# picoKey_2401.net
KiCad netlist of a schematic drawn in EAGLE
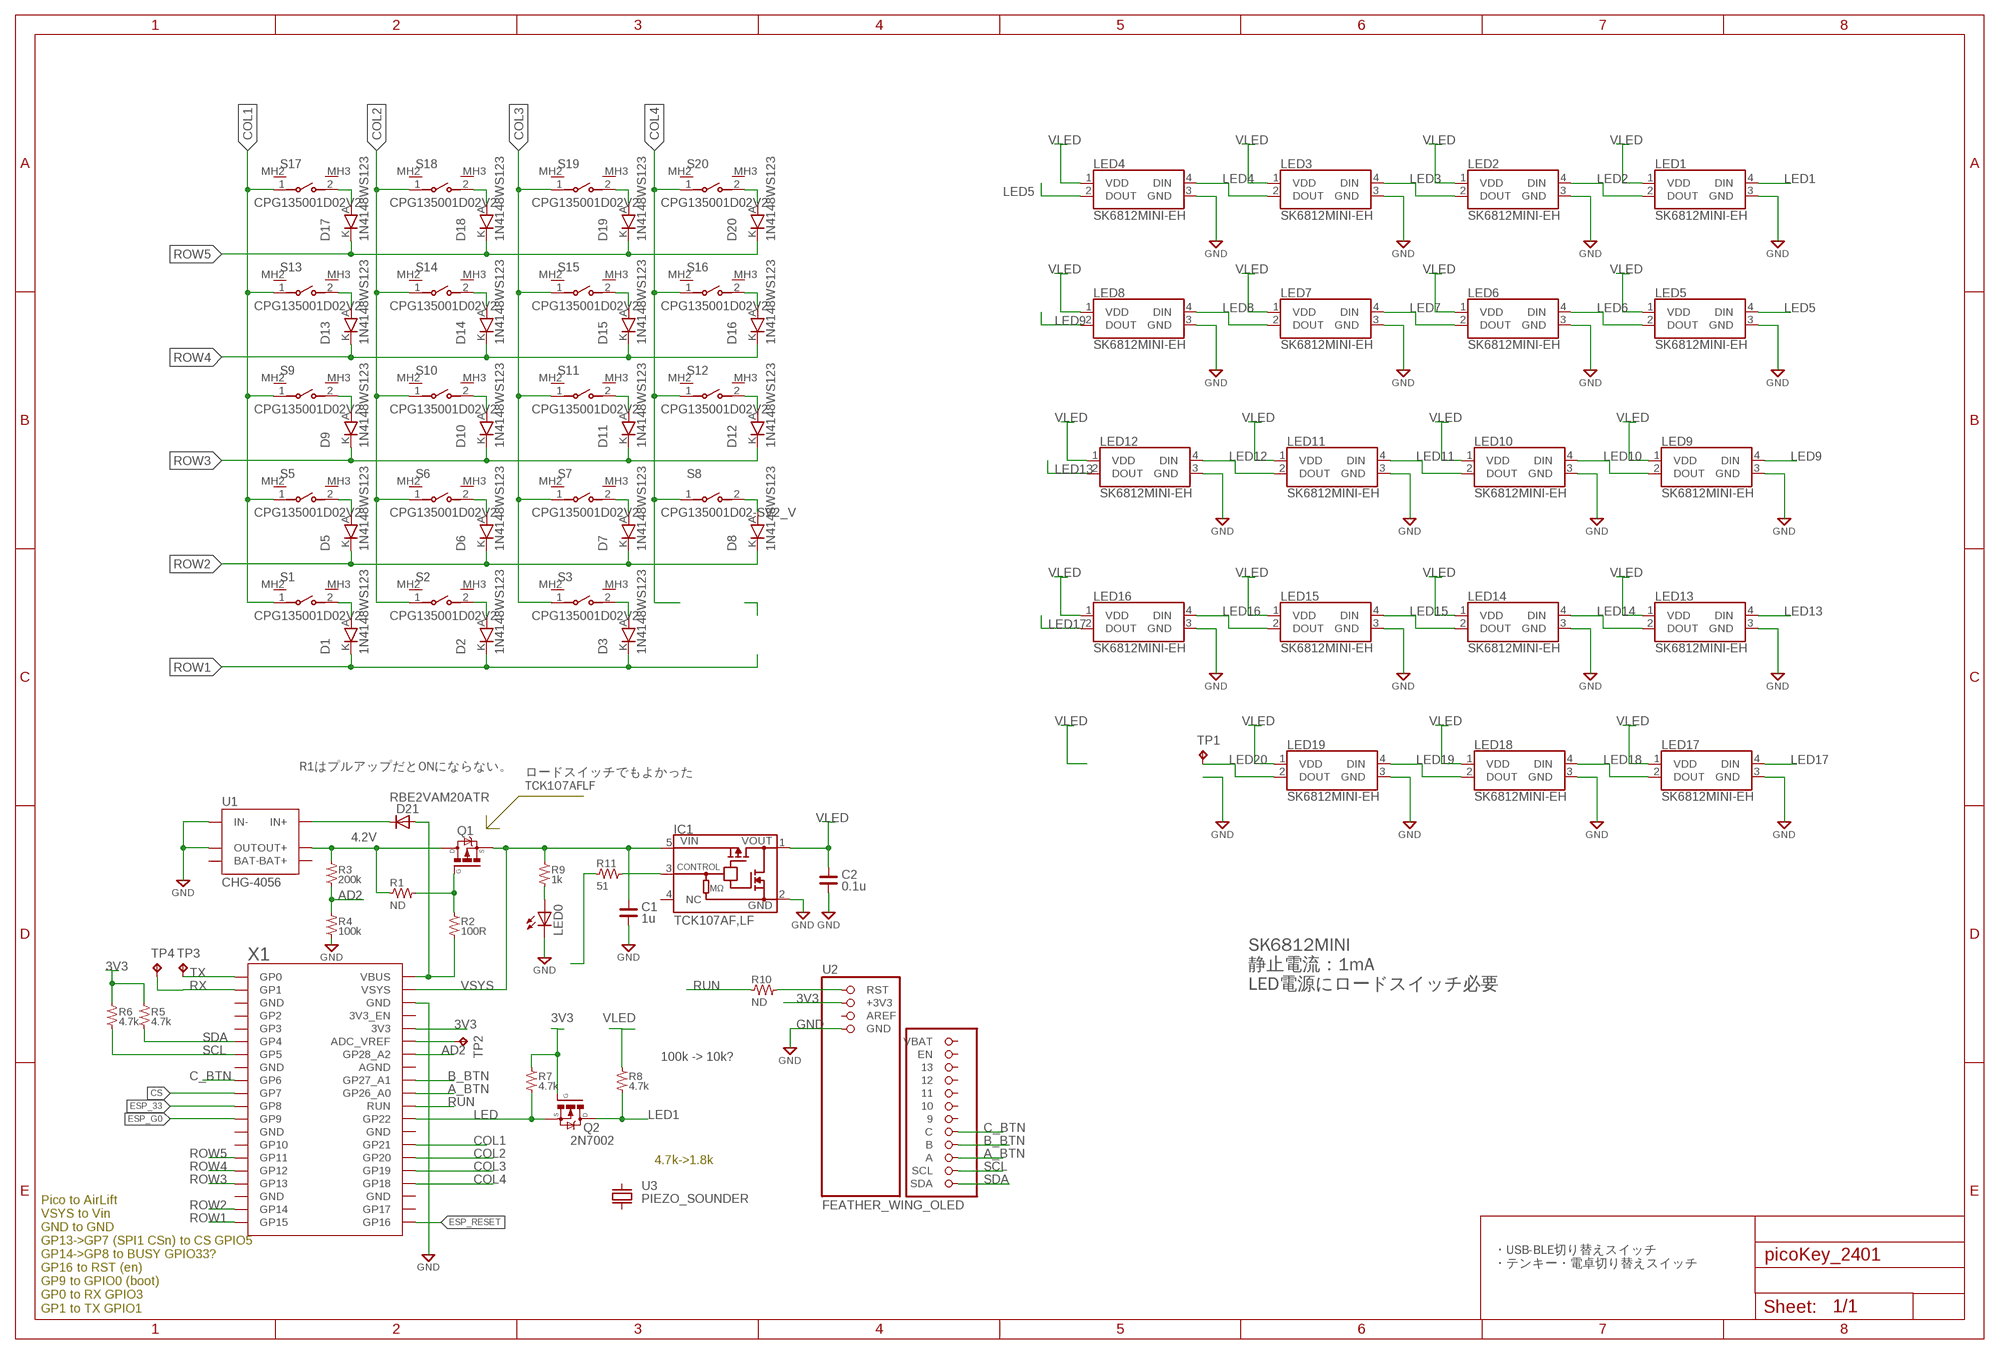
[diagram p0: schematic, sheet 1]

(export (version "E")
  (design (tool "Eeschema 10.0.6"))
  (components
    (comp (ref "C1")
      (value "1u")
      (footprint "eagle-import:C0603")
      (libsource (lib "eagle-import") (part "C_0603"))
    )
    (comp (ref "C2")
      (value "0.1u")
      (footprint "eagle-import:C0603")
      (libsource (lib "eagle-import") (part "C_0603"))
    )
    (comp (ref "D1")
      (value "1N4148WS123")
      (footprint "eagle-import:SOD-123")
      (libsource (lib "eagle-import") (part "1N4148WS123"))
    )
    (comp (ref "D2")
      (value "1N4148WS123")
      (footprint "eagle-import:SOD-123")
      (libsource (lib "eagle-import") (part "1N4148WS123"))
    )
    (comp (ref "D3")
      (value "1N4148WS123")
      (footprint "eagle-import:SOD-123")
      (libsource (lib "eagle-import") (part "1N4148WS123"))
    )
    (comp (ref "D5")
      (value "1N4148WS123")
      (footprint "eagle-import:SOD-123")
      (libsource (lib "eagle-import") (part "1N4148WS123"))
    )
    (comp (ref "D6")
      (value "1N4148WS123")
      (footprint "eagle-import:SOD-123")
      (libsource (lib "eagle-import") (part "1N4148WS123"))
    )
    (comp (ref "D7")
      (value "1N4148WS123")
      (footprint "eagle-import:SOD-123")
      (libsource (lib "eagle-import") (part "1N4148WS123"))
    )
    (comp (ref "D8")
      (value "1N4148WS123")
      (footprint "eagle-import:SOD-123")
      (libsource (lib "eagle-import") (part "1N4148WS123"))
    )
    (comp (ref "D9")
      (value "1N4148WS123")
      (footprint "eagle-import:SOD-123")
      (libsource (lib "eagle-import") (part "1N4148WS123"))
    )
    (comp (ref "D10")
      (value "1N4148WS123")
      (footprint "eagle-import:SOD-123")
      (libsource (lib "eagle-import") (part "1N4148WS123"))
    )
    (comp (ref "D11")
      (value "1N4148WS123")
      (footprint "eagle-import:SOD-123")
      (libsource (lib "eagle-import") (part "1N4148WS123"))
    )
    (comp (ref "D12")
      (value "1N4148WS123")
      (footprint "eagle-import:SOD-123")
      (libsource (lib "eagle-import") (part "1N4148WS123"))
    )
    (comp (ref "D13")
      (value "1N4148WS123")
      (footprint "eagle-import:SOD-123")
      (libsource (lib "eagle-import") (part "1N4148WS123"))
    )
    (comp (ref "D14")
      (value "1N4148WS123")
      (footprint "eagle-import:SOD-123")
      (libsource (lib "eagle-import") (part "1N4148WS123"))
    )
    (comp (ref "D15")
      (value "1N4148WS123")
      (footprint "eagle-import:SOD-123")
      (libsource (lib "eagle-import") (part "1N4148WS123"))
    )
    (comp (ref "D16")
      (value "1N4148WS123")
      (footprint "eagle-import:SOD-123")
      (libsource (lib "eagle-import") (part "1N4148WS123"))
    )
    (comp (ref "D17")
      (value "1N4148WS123")
      (footprint "eagle-import:SOD-123")
      (libsource (lib "eagle-import") (part "1N4148WS123"))
    )
    (comp (ref "D18")
      (value "1N4148WS123")
      (footprint "eagle-import:SOD-123")
      (libsource (lib "eagle-import") (part "1N4148WS123"))
    )
    (comp (ref "D19")
      (value "1N4148WS123")
      (footprint "eagle-import:SOD-123")
      (libsource (lib "eagle-import") (part "1N4148WS123"))
    )
    (comp (ref "D20")
      (value "1N4148WS123")
      (footprint "eagle-import:SOD-123")
      (libsource (lib "eagle-import") (part "1N4148WS123"))
    )
    (comp (ref "D21")
      (value "RBE2VAM20ATR")
      (footprint "eagle-import:SOD-123")
      (libsource (lib "eagle-import") (part "DIODE123"))
    )
    (comp (ref "IC1")
      (value "TCK107AF,LF")
      (footprint "eagle-import:SMV_1")
      (fields
        (field (name "ARROW_PART_NUMBER") "TCK106AF,LF")
        (field (name "MOUSER_PART_NUMBER") "757-TCK106AFLF")
      )
      (libsource (lib "eagle-import") (part "TCK107AF,LF"))
    )
    (comp (ref "LED0")
      (value "LEDCHIP-LED0603")
      (footprint "eagle-import:CHIP-LED0603")
      (libsource (lib "eagle-import") (part "LEDCHIP-LED0603"))
    )
    (comp (ref "LED1")
      (value "SK6812MINI-EH")
      (footprint "eagle-import:SK6812MINIE-H")
      (libsource (lib "eagle-import") (part "SK6812MINI-EH"))
    )
    (comp (ref "LED2")
      (value "SK6812MINI-EH")
      (footprint "eagle-import:SK6812MINIE-H")
      (libsource (lib "eagle-import") (part "SK6812MINI-EH"))
    )
    (comp (ref "LED3")
      (value "SK6812MINI-EH")
      (footprint "eagle-import:SK6812MINIE-H")
      (libsource (lib "eagle-import") (part "SK6812MINI-EH"))
    )
    (comp (ref "LED4")
      (value "SK6812MINI-EH")
      (footprint "eagle-import:SK6812MINIE-H")
      (libsource (lib "eagle-import") (part "SK6812MINI-EH"))
    )
    (comp (ref "LED5")
      (value "SK6812MINI-EH")
      (footprint "eagle-import:SK6812MINIE-H")
      (libsource (lib "eagle-import") (part "SK6812MINI-EH"))
    )
    (comp (ref "LED6")
      (value "SK6812MINI-EH")
      (footprint "eagle-import:SK6812MINIE-H")
      (libsource (lib "eagle-import") (part "SK6812MINI-EH"))
    )
    (comp (ref "LED7")
      (value "SK6812MINI-EH")
      (footprint "eagle-import:SK6812MINIE-H")
      (libsource (lib "eagle-import") (part "SK6812MINI-EH"))
    )
    (comp (ref "LED8")
      (value "SK6812MINI-EH")
      (footprint "eagle-import:SK6812MINIE-H")
      (libsource (lib "eagle-import") (part "SK6812MINI-EH"))
    )
    (comp (ref "LED9")
      (value "SK6812MINI-EH")
      (footprint "eagle-import:SK6812MINIE-H")
      (libsource (lib "eagle-import") (part "SK6812MINI-EH"))
    )
    (comp (ref "LED10")
      (value "SK6812MINI-EH")
      (footprint "eagle-import:SK6812MINIE-H")
      (libsource (lib "eagle-import") (part "SK6812MINI-EH"))
    )
    (comp (ref "LED11")
      (value "SK6812MINI-EH")
      (footprint "eagle-import:SK6812MINIE-H")
      (libsource (lib "eagle-import") (part "SK6812MINI-EH"))
    )
    (comp (ref "LED12")
      (value "SK6812MINI-EH")
      (footprint "eagle-import:SK6812MINIE-H")
      (libsource (lib "eagle-import") (part "SK6812MINI-EH"))
    )
    (comp (ref "LED13")
      (value "SK6812MINI-EH")
      (footprint "eagle-import:SK6812MINIE-H")
      (libsource (lib "eagle-import") (part "SK6812MINI-EH"))
    )
    (comp (ref "LED14")
      (value "SK6812MINI-EH")
      (footprint "eagle-import:SK6812MINIE-H")
      (libsource (lib "eagle-import") (part "SK6812MINI-EH"))
    )
    (comp (ref "LED15")
      (value "SK6812MINI-EH")
      (footprint "eagle-import:SK6812MINIE-H")
      (libsource (lib "eagle-import") (part "SK6812MINI-EH"))
    )
    (comp (ref "LED16")
      (value "SK6812MINI-EH")
      (footprint "eagle-import:SK6812MINIE-H")
      (libsource (lib "eagle-import") (part "SK6812MINI-EH"))
    )
    (comp (ref "LED17")
      (value "SK6812MINI-EH")
      (footprint "eagle-import:SK6812MINIE-H")
      (libsource (lib "eagle-import") (part "SK6812MINI-EH"))
    )
    (comp (ref "LED18")
      (value "SK6812MINI-EH")
      (footprint "eagle-import:SK6812MINIE-H")
      (libsource (lib "eagle-import") (part "SK6812MINI-EH"))
    )
    (comp (ref "LED19")
      (value "SK6812MINI-EH")
      (footprint "eagle-import:SK6812MINIE-H")
      (libsource (lib "eagle-import") (part "SK6812MINI-EH"))
    )
    (comp (ref "Q1")
      (value "MOSFET-P")
      (footprint "eagle-import:SOT-23")
      (libsource (lib "eagle-import") (part "MOSFET-P"))
    )
    (comp (ref "Q2")
      (value "2N7002")
      (footprint "eagle-import:SOT-23")
      (libsource (lib "eagle-import") (part "MOSFET-NSOT-23"))
    )
    (comp (ref "R1")
      (value "ND")
      (footprint "eagle-import:R0603")
      (libsource (lib "eagle-import") (part "R_0603"))
    )
    (comp (ref "R2")
      (value "100R")
      (footprint "eagle-import:R0603")
      (libsource (lib "eagle-import") (part "R_0603"))
    )
    (comp (ref "R3")
      (value "200k")
      (footprint "eagle-import:R0603")
      (libsource (lib "eagle-import") (part "R_0603"))
    )
    (comp (ref "R4")
      (value "100k")
      (footprint "eagle-import:R0603")
      (libsource (lib "eagle-import") (part "R_0603"))
    )
    (comp (ref "R5")
      (value "4.7k")
      (footprint "eagle-import:R0603")
      (libsource (lib "eagle-import") (part "R_0603"))
    )
    (comp (ref "R6")
      (value "4.7k")
      (footprint "eagle-import:R0603")
      (libsource (lib "eagle-import") (part "R_0603"))
    )
    (comp (ref "R7")
      (value "4.7k")
      (footprint "eagle-import:R0603")
      (libsource (lib "eagle-import") (part "R_0603"))
    )
    (comp (ref "R8")
      (value "4.7k")
      (footprint "eagle-import:R0603")
      (libsource (lib "eagle-import") (part "R_0603"))
    )
    (comp (ref "R9")
      (value "1k")
      (footprint "eagle-import:R0603")
      (libsource (lib "eagle-import") (part "R_0603"))
    )
    (comp (ref "R10")
      (value "ND")
      (footprint "eagle-import:R0603")
      (libsource (lib "eagle-import") (part "R_0603"))
    )
    (comp (ref "R11")
      (value "51")
      (footprint "eagle-import:R0603")
      (libsource (lib "eagle-import") (part "R_0603"))
    )
    (comp (ref "S1")
      (value "CPG135001D02V2")
      (footprint "eagle-import:KAILH_CHOC_V2")
      (libsource (lib "eagle-import") (part "CPG135001D02V2"))
    )
    (comp (ref "S2")
      (value "CPG135001D02V2")
      (footprint "eagle-import:KAILH_CHOC_V2")
      (libsource (lib "eagle-import") (part "CPG135001D02V2"))
    )
    (comp (ref "S3")
      (value "CPG135001D02V2")
      (footprint "eagle-import:KAILH_CHOC_V2")
      (libsource (lib "eagle-import") (part "CPG135001D02V2"))
    )
    (comp (ref "S5")
      (value "CPG135001D02V2")
      (footprint "eagle-import:KAILH_CHOC_V2")
      (libsource (lib "eagle-import") (part "CPG135001D02V2"))
    )
    (comp (ref "S6")
      (value "CPG135001D02V2")
      (footprint "eagle-import:KAILH_CHOC_V2")
      (libsource (lib "eagle-import") (part "CPG135001D02V2"))
    )
    (comp (ref "S7")
      (value "CPG135001D02V2")
      (footprint "eagle-import:KAILH_CHOC_V2")
      (libsource (lib "eagle-import") (part "CPG135001D02V2"))
    )
    (comp (ref "S8")
      (value "CPG135001D02-SV2_V")
      (footprint "eagle-import:KAILH_CHOC_V2_V")
      (libsource (lib "eagle-import") (part "CPG135001D02-SV2_V"))
    )
    (comp (ref "S9")
      (value "CPG135001D02V2")
      (footprint "eagle-import:KAILH_CHOC_V2")
      (libsource (lib "eagle-import") (part "CPG135001D02V2"))
    )
    (comp (ref "S10")
      (value "CPG135001D02V2")
      (footprint "eagle-import:KAILH_CHOC_V2")
      (libsource (lib "eagle-import") (part "CPG135001D02V2"))
    )
    (comp (ref "S11")
      (value "CPG135001D02V2")
      (footprint "eagle-import:KAILH_CHOC_V2")
      (libsource (lib "eagle-import") (part "CPG135001D02V2"))
    )
    (comp (ref "S12")
      (value "CPG135001D02V2")
      (footprint "eagle-import:KAILH_CHOC_V2")
      (libsource (lib "eagle-import") (part "CPG135001D02V2"))
    )
    (comp (ref "S13")
      (value "CPG135001D02V2")
      (footprint "eagle-import:KAILH_CHOC_V2")
      (libsource (lib "eagle-import") (part "CPG135001D02V2"))
    )
    (comp (ref "S14")
      (value "CPG135001D02V2")
      (footprint "eagle-import:KAILH_CHOC_V2")
      (libsource (lib "eagle-import") (part "CPG135001D02V2"))
    )
    (comp (ref "S15")
      (value "CPG135001D02V2")
      (footprint "eagle-import:KAILH_CHOC_V2")
      (libsource (lib "eagle-import") (part "CPG135001D02V2"))
    )
    (comp (ref "S16")
      (value "CPG135001D02V2")
      (footprint "eagle-import:KAILH_CHOC_V2")
      (libsource (lib "eagle-import") (part "CPG135001D02V2"))
    )
    (comp (ref "S17")
      (value "CPG135001D02V2")
      (footprint "eagle-import:KAILH_CHOC_V2")
      (libsource (lib "eagle-import") (part "CPG135001D02V2"))
    )
    (comp (ref "S18")
      (value "CPG135001D02V2")
      (footprint "eagle-import:KAILH_CHOC_V2")
      (libsource (lib "eagle-import") (part "CPG135001D02V2"))
    )
    (comp (ref "S19")
      (value "CPG135001D02V2")
      (footprint "eagle-import:KAILH_CHOC_V2")
      (libsource (lib "eagle-import") (part "CPG135001D02V2"))
    )
    (comp (ref "S20")
      (value "CPG135001D02V2")
      (footprint "eagle-import:KAILH_CHOC_V2")
      (libsource (lib "eagle-import") (part "CPG135001D02V2"))
    )
    (comp (ref "TP1")
      (value "TPTP06R")
      (footprint "eagle-import:TP06R")
      (libsource (lib "eagle-import") (part "TPTP06R"))
    )
    (comp (ref "TP2")
      (value "TPTP06R")
      (footprint "eagle-import:TP06R")
      (libsource (lib "eagle-import") (part "TPTP06R"))
    )
    (comp (ref "TP3")
      (value "TPTP06R")
      (footprint "eagle-import:TP06R")
      (libsource (lib "eagle-import") (part "TPTP06R"))
    )
    (comp (ref "TP4")
      (value "TPTP06R")
      (footprint "eagle-import:TP06R")
      (libsource (lib "eagle-import") (part "TPTP06R"))
    )
    (comp (ref "U1")
      (value "CHG-4056")
      (footprint "eagle-import:CHG-4056")
      (libsource (lib "eagle-import") (part "CHG-4056"))
    )
    (comp (ref "U2")
      (value "FEATHER_WING_OLED")
      (footprint "eagle-import:FEATHER_WING_OLED")
      (libsource (lib "eagle-import") (part "FEATHER_WING_OLED"))
    )
    (comp (ref "U3")
      (value "PIEZO_SOUNDER")
      (footprint "eagle-import:DINAMIC-SPK")
      (libsource (lib "eagle-import") (part "PIEZO_SOUNDER"))
    )
    (comp (ref "X1")
      (value "RASPBERRYPI_PICO_RPI_PICO_MY-MY")
      (footprint "eagle-import:RASPBERRYPI_PICO_RPI_PICO_MY")
      (libsource (lib "eagle-import") (part "RASPBERRYPI_PICO_RPI_PICO_MY-MY"))
    )
  )
  (nets
    (net (code "1") (name "/3V3") (class "Default")
      (node (ref "Q2") (pin "3") (pinfunction "G_3") (pintype "passive"))
      (node (ref "R5") (pin "2") (pinfunction "2_2") (pintype "passive"))
      (node (ref "R6") (pin "2") (pinfunction "2_2") (pintype "passive"))
      (node (ref "R7") (pin "1") (pinfunction "1_1") (pintype "passive"))
      (node (ref "U2") (pin "15") (pinfunction "+3V3_15") (pintype "passive"))
      (node (ref "X1") (pin "3V3") (pinfunction "3V3_3V3") (pintype "bidirectional"))
    )
    (net (code "2") (name "/4.2V") (class "Default")
      (node (ref "Q1") (pin "2") (pinfunction "D_2") (pintype "passive"))
      (node (ref "R1") (pin "1") (pinfunction "1_1") (pintype "passive"))
      (node (ref "R3") (pin "2") (pinfunction "2_2") (pintype "passive"))
      (node (ref "U1") (pin "OUT+") (pinfunction "OUT+_OUT+") (pintype "bidirectional"))
    )
    (net (code "3") (name "/AD2") (class "Default")
      (node (ref "R3") (pin "1") (pinfunction "1_1") (pintype "passive"))
      (node (ref "R4") (pin "2") (pinfunction "2_2") (pintype "passive"))
      (node (ref "X1") (pin "GP28_A2") (pinfunction "GP28_A2_GP28_A2") (pintype "bidirectional"))
    )
    (net (code "4") (name "/A_BTN") (class "Default")
      (node (ref "U2") (pin "26") (pinfunction "A_26") (pintype "passive"))
      (node (ref "X1") (pin "GP26_A0") (pinfunction "GP26_A0_GP26_A0") (pintype "bidirectional"))
    )
    (net (code "5") (name "/B_BTN") (class "Default")
      (node (ref "U2") (pin "25") (pinfunction "B_25") (pintype "passive"))
      (node (ref "X1") (pin "GP27_A1") (pinfunction "GP27_A1_GP27_A1") (pintype "bidirectional"))
    )
    (net (code "6") (name "/C_BTN") (class "Default")
      (node (ref "U2") (pin "24") (pinfunction "C_24") (pintype "passive"))
      (node (ref "X1") (pin "GP6") (pinfunction "GP6_GP6") (pintype "bidirectional"))
    )
    (net (code "7") (name "/LED") (class "Default")
      (node (ref "Q2") (pin "1") (pinfunction "S_1") (pintype "passive"))
      (node (ref "R7") (pin "2") (pinfunction "2_2") (pintype "passive"))
      (node (ref "X1") (pin "GP22") (pinfunction "GP22_GP22") (pintype "bidirectional"))
    )
    (net (code "8") (name "/LED1") (class "Default")
      (node (ref "LED1") (pin "4") (pinfunction "DIN_4") (pintype "bidirectional"))
      (node (ref "Q2") (pin "2") (pinfunction "D_2") (pintype "passive"))
      (node (ref "R8") (pin "2") (pinfunction "2_2") (pintype "passive"))
    )
    (net (code "9") (name "/LED2") (class "Default")
      (node (ref "LED1") (pin "2") (pinfunction "DOUT_2") (pintype "bidirectional"))
      (node (ref "LED2") (pin "4") (pinfunction "DIN_4") (pintype "bidirectional"))
    )
    (net (code "10") (name "/LED3") (class "Default")
      (node (ref "LED2") (pin "2") (pinfunction "DOUT_2") (pintype "bidirectional"))
      (node (ref "LED3") (pin "4") (pinfunction "DIN_4") (pintype "bidirectional"))
    )
    (net (code "11") (name "/LED4") (class "Default")
      (node (ref "LED3") (pin "2") (pinfunction "DOUT_2") (pintype "bidirectional"))
      (node (ref "LED4") (pin "4") (pinfunction "DIN_4") (pintype "bidirectional"))
    )
    (net (code "12") (name "/LED5") (class "Default")
      (node (ref "LED4") (pin "2") (pinfunction "DOUT_2") (pintype "bidirectional"))
      (node (ref "LED5") (pin "4") (pinfunction "DIN_4") (pintype "bidirectional"))
    )
    (net (code "13") (name "/LED6") (class "Default")
      (node (ref "LED5") (pin "2") (pinfunction "DOUT_2") (pintype "bidirectional"))
      (node (ref "LED6") (pin "4") (pinfunction "DIN_4") (pintype "bidirectional"))
    )
    (net (code "14") (name "/LED7") (class "Default")
      (node (ref "LED6") (pin "2") (pinfunction "DOUT_2") (pintype "bidirectional"))
      (node (ref "LED7") (pin "4") (pinfunction "DIN_4") (pintype "bidirectional"))
    )
    (net (code "15") (name "/LED8") (class "Default")
      (node (ref "LED7") (pin "2") (pinfunction "DOUT_2") (pintype "bidirectional"))
      (node (ref "LED8") (pin "4") (pinfunction "DIN_4") (pintype "bidirectional"))
    )
    (net (code "16") (name "/LED9") (class "Default")
      (node (ref "LED8") (pin "2") (pinfunction "DOUT_2") (pintype "bidirectional"))
      (node (ref "LED9") (pin "4") (pinfunction "DIN_4") (pintype "bidirectional"))
    )
    (net (code "17") (name "/LED10") (class "Default")
      (node (ref "LED10") (pin "4") (pinfunction "DIN_4") (pintype "bidirectional"))
      (node (ref "LED9") (pin "2") (pinfunction "DOUT_2") (pintype "bidirectional"))
    )
    (net (code "18") (name "/LED11") (class "Default")
      (node (ref "LED10") (pin "2") (pinfunction "DOUT_2") (pintype "bidirectional"))
      (node (ref "LED11") (pin "4") (pinfunction "DIN_4") (pintype "bidirectional"))
    )
    (net (code "19") (name "/LED12") (class "Default")
      (node (ref "LED11") (pin "2") (pinfunction "DOUT_2") (pintype "bidirectional"))
      (node (ref "LED12") (pin "4") (pinfunction "DIN_4") (pintype "bidirectional"))
    )
    (net (code "20") (name "/LED13") (class "Default")
      (node (ref "LED12") (pin "2") (pinfunction "DOUT_2") (pintype "bidirectional"))
      (node (ref "LED13") (pin "4") (pinfunction "DIN_4") (pintype "bidirectional"))
    )
    (net (code "21") (name "/LED14") (class "Default")
      (node (ref "LED13") (pin "2") (pinfunction "DOUT_2") (pintype "bidirectional"))
      (node (ref "LED14") (pin "4") (pinfunction "DIN_4") (pintype "bidirectional"))
    )
    (net (code "22") (name "/LED15") (class "Default")
      (node (ref "LED14") (pin "2") (pinfunction "DOUT_2") (pintype "bidirectional"))
      (node (ref "LED15") (pin "4") (pinfunction "DIN_4") (pintype "bidirectional"))
    )
    (net (code "23") (name "/LED16") (class "Default")
      (node (ref "LED15") (pin "2") (pinfunction "DOUT_2") (pintype "bidirectional"))
      (node (ref "LED16") (pin "4") (pinfunction "DIN_4") (pintype "bidirectional"))
    )
    (net (code "24") (name "/LED17") (class "Default")
      (node (ref "LED16") (pin "2") (pinfunction "DOUT_2") (pintype "bidirectional"))
      (node (ref "LED17") (pin "4") (pinfunction "DIN_4") (pintype "bidirectional"))
    )
    (net (code "25") (name "/LED18") (class "Default")
      (node (ref "LED17") (pin "2") (pinfunction "DOUT_2") (pintype "bidirectional"))
      (node (ref "LED18") (pin "4") (pinfunction "DIN_4") (pintype "bidirectional"))
    )
    (net (code "26") (name "/LED19") (class "Default")
      (node (ref "LED18") (pin "2") (pinfunction "DOUT_2") (pintype "bidirectional"))
      (node (ref "LED19") (pin "4") (pinfunction "DIN_4") (pintype "bidirectional"))
    )
    (net (code "27") (name "/LED20") (class "Default")
      (node (ref "LED19") (pin "2") (pinfunction "DOUT_2") (pintype "bidirectional"))
      (node (ref "TP1") (pin "TP") (pinfunction "TP_TP") (pintype "input"))
    )
    (net (code "28") (name "/RUN") (class "Default")
      (node (ref "R10") (pin "1") (pinfunction "1_1") (pintype "passive"))
      (node (ref "X1") (pin "RUN") (pinfunction "RUN_RUN") (pintype "bidirectional"))
    )
    (net (code "29") (name "/RX") (class "Default")
      (node (ref "TP4") (pin "TP") (pinfunction "TP_TP") (pintype "input"))
      (node (ref "X1") (pin "GP1") (pinfunction "GP1_GP1") (pintype "bidirectional"))
    )
    (net (code "30") (name "/SCL") (class "Default")
      (node (ref "R6") (pin "1") (pinfunction "1_1") (pintype "passive"))
      (node (ref "U2") (pin "27") (pinfunction "SCL_27") (pintype "passive"))
      (node (ref "X1") (pin "GP5") (pinfunction "GP5_GP5") (pintype "bidirectional"))
    )
    (net (code "31") (name "/SDA") (class "Default")
      (node (ref "R5") (pin "1") (pinfunction "1_1") (pintype "passive"))
      (node (ref "U2") (pin "28") (pinfunction "SDA_28") (pintype "passive"))
      (node (ref "X1") (pin "GP4") (pinfunction "GP4_GP4") (pintype "bidirectional"))
    )
    (net (code "32") (name "/TX") (class "Default")
      (node (ref "TP3") (pin "TP") (pinfunction "TP_TP") (pintype "input"))
      (node (ref "X1") (pin "GP0") (pinfunction "GP0_GP0") (pintype "bidirectional"))
    )
    (net (code "33") (name "/VLED") (class "Default")
      (node (ref "C2") (pin "2") (pinfunction "2_2") (pintype "passive"))
      (node (ref "IC1") (pin "1") (pinfunction "VOUT_1") (pintype "bidirectional"))
      (node (ref "LED1") (pin "1") (pinfunction "VDD_1") (pintype "bidirectional"))
      (node (ref "LED10") (pin "1") (pinfunction "VDD_1") (pintype "bidirectional"))
      (node (ref "LED11") (pin "1") (pinfunction "VDD_1") (pintype "bidirectional"))
      (node (ref "LED12") (pin "1") (pinfunction "VDD_1") (pintype "bidirectional"))
      (node (ref "LED13") (pin "1") (pinfunction "VDD_1") (pintype "bidirectional"))
      (node (ref "LED14") (pin "1") (pinfunction "VDD_1") (pintype "bidirectional"))
      (node (ref "LED15") (pin "1") (pinfunction "VDD_1") (pintype "bidirectional"))
      (node (ref "LED16") (pin "1") (pinfunction "VDD_1") (pintype "bidirectional"))
      (node (ref "LED17") (pin "1") (pinfunction "VDD_1") (pintype "bidirectional"))
      (node (ref "LED18") (pin "1") (pinfunction "VDD_1") (pintype "bidirectional"))
      (node (ref "LED19") (pin "1") (pinfunction "VDD_1") (pintype "bidirectional"))
      (node (ref "LED2") (pin "1") (pinfunction "VDD_1") (pintype "bidirectional"))
      (node (ref "LED3") (pin "1") (pinfunction "VDD_1") (pintype "bidirectional"))
      (node (ref "LED4") (pin "1") (pinfunction "VDD_1") (pintype "bidirectional"))
      (node (ref "LED5") (pin "1") (pinfunction "VDD_1") (pintype "bidirectional"))
      (node (ref "LED6") (pin "1") (pinfunction "VDD_1") (pintype "bidirectional"))
      (node (ref "LED7") (pin "1") (pinfunction "VDD_1") (pintype "bidirectional"))
      (node (ref "LED8") (pin "1") (pinfunction "VDD_1") (pintype "bidirectional"))
      (node (ref "LED9") (pin "1") (pinfunction "VDD_1") (pintype "bidirectional"))
      (node (ref "R8") (pin "1") (pinfunction "1_1") (pintype "passive"))
    )
    (net (code "34") (name "/VSYS") (class "Default")
      (node (ref "C1") (pin "2") (pinfunction "2_2") (pintype "passive"))
      (node (ref "IC1") (pin "5") (pinfunction "VIN_5") (pintype "bidirectional"))
      (node (ref "Q1") (pin "1") (pinfunction "S_1") (pintype "passive"))
      (node (ref "R9") (pin "1") (pinfunction "1_1") (pintype "passive"))
      (node (ref "X1") (pin "VSYS") (pinfunction "VSYS_VSYS") (pintype "bidirectional"))
    )
    (net (code "35") (name "COL1") (class "Default")
      (node (ref "S1") (pin "1") (pinfunction "1_1") (pintype "bidirectional"))
      (node (ref "S13") (pin "1") (pinfunction "1_1") (pintype "bidirectional"))
      (node (ref "S17") (pin "1") (pinfunction "1_1") (pintype "bidirectional"))
      (node (ref "S5") (pin "1") (pinfunction "1_1") (pintype "bidirectional"))
      (node (ref "S9") (pin "1") (pinfunction "1_1") (pintype "bidirectional"))
      (node (ref "X1") (pin "GP21") (pinfunction "GP21_GP21") (pintype "bidirectional"))
    )
    (net (code "36") (name "COL2") (class "Default")
      (node (ref "S10") (pin "1") (pinfunction "1_1") (pintype "bidirectional"))
      (node (ref "S14") (pin "1") (pinfunction "1_1") (pintype "bidirectional"))
      (node (ref "S18") (pin "1") (pinfunction "1_1") (pintype "bidirectional"))
      (node (ref "S2") (pin "1") (pinfunction "1_1") (pintype "bidirectional"))
      (node (ref "S6") (pin "1") (pinfunction "1_1") (pintype "bidirectional"))
      (node (ref "X1") (pin "GP20") (pinfunction "GP20_GP20") (pintype "bidirectional"))
    )
    (net (code "37") (name "COL3") (class "Default")
      (node (ref "S11") (pin "1") (pinfunction "1_1") (pintype "bidirectional"))
      (node (ref "S15") (pin "1") (pinfunction "1_1") (pintype "bidirectional"))
      (node (ref "S19") (pin "1") (pinfunction "1_1") (pintype "bidirectional"))
      (node (ref "S3") (pin "1") (pinfunction "1_1") (pintype "bidirectional"))
      (node (ref "S7") (pin "1") (pinfunction "1_1") (pintype "bidirectional"))
      (node (ref "X1") (pin "GP19") (pinfunction "GP19_GP19") (pintype "bidirectional"))
    )
    (net (code "38") (name "COL4") (class "Default")
      (node (ref "S12") (pin "1") (pinfunction "1_1") (pintype "bidirectional"))
      (node (ref "S16") (pin "1") (pinfunction "1_1") (pintype "bidirectional"))
      (node (ref "S20") (pin "1") (pinfunction "1_1") (pintype "bidirectional"))
      (node (ref "S8") (pin "1") (pinfunction "1_1") (pintype "bidirectional"))
      (node (ref "X1") (pin "GP18") (pinfunction "GP18_GP18") (pintype "bidirectional"))
    )
    (net (code "39") (name "CS") (class "Default")
      (node (ref "X1") (pin "GP7") (pinfunction "GP7_GP7") (pintype "bidirectional"))
    )
    (net (code "40") (name "ESP_33") (class "Default")
      (node (ref "X1") (pin "GP8") (pinfunction "GP8_GP8") (pintype "bidirectional"))
    )
    (net (code "41") (name "ESP_G0") (class "Default")
      (node (ref "X1") (pin "GP9") (pinfunction "GP9_GP9") (pintype "bidirectional"))
    )
    (net (code "42") (name "ESP_RESET") (class "Default")
      (node (ref "X1") (pin "GP16") (pinfunction "GP16_GP16") (pintype "bidirectional"))
    )
    (net (code "43") (name "G") (class "Default")
      (node (ref "C1") (pin "1") (pinfunction "1_1") (pintype "passive"))
      (node (ref "C2") (pin "1") (pinfunction "1_1") (pintype "passive"))
      (node (ref "IC1") (pin "2") (pinfunction "GND_2") (pintype "bidirectional"))
      (node (ref "LED0") (pin "C") (pinfunction "C_C") (pintype "passive"))
      (node (ref "LED1") (pin "3") (pinfunction "GND_3") (pintype "bidirectional"))
      (node (ref "LED10") (pin "3") (pinfunction "GND_3") (pintype "bidirectional"))
      (node (ref "LED11") (pin "3") (pinfunction "GND_3") (pintype "bidirectional"))
      (node (ref "LED12") (pin "3") (pinfunction "GND_3") (pintype "bidirectional"))
      (node (ref "LED13") (pin "3") (pinfunction "GND_3") (pintype "bidirectional"))
      (node (ref "LED14") (pin "3") (pinfunction "GND_3") (pintype "bidirectional"))
      (node (ref "LED15") (pin "3") (pinfunction "GND_3") (pintype "bidirectional"))
      (node (ref "LED16") (pin "3") (pinfunction "GND_3") (pintype "bidirectional"))
      (node (ref "LED17") (pin "3") (pinfunction "GND_3") (pintype "bidirectional"))
      (node (ref "LED18") (pin "3") (pinfunction "GND_3") (pintype "bidirectional"))
      (node (ref "LED19") (pin "3") (pinfunction "GND_3") (pintype "bidirectional"))
      (node (ref "LED2") (pin "3") (pinfunction "GND_3") (pintype "bidirectional"))
      (node (ref "LED3") (pin "3") (pinfunction "GND_3") (pintype "bidirectional"))
      (node (ref "LED4") (pin "3") (pinfunction "GND_3") (pintype "bidirectional"))
      (node (ref "LED5") (pin "3") (pinfunction "GND_3") (pintype "bidirectional"))
      (node (ref "LED6") (pin "3") (pinfunction "GND_3") (pintype "bidirectional"))
      (node (ref "LED7") (pin "3") (pinfunction "GND_3") (pintype "bidirectional"))
      (node (ref "LED8") (pin "3") (pinfunction "GND_3") (pintype "bidirectional"))
      (node (ref "LED9") (pin "3") (pinfunction "GND_3") (pintype "bidirectional"))
      (node (ref "R4") (pin "1") (pinfunction "1_1") (pintype "passive"))
      (node (ref "U1") (pin "IN-") (pinfunction "IN-_IN-") (pintype "bidirectional"))
      (node (ref "U1") (pin "OUT-") (pinfunction "OUT-_OUT-") (pintype "bidirectional"))
      (node (ref "U2") (pin "13") (pinfunction "GND_13") (pintype "passive"))
      (node (ref "X1") (pin "GND@8") (pinfunction "GND_GND@8") (pintype "bidirectional"))
    )
    (net (code "44") (name "Net-(D1-PadA)") (class "Default")
      (node (ref "D1") (pin "A") (pinfunction "A_A") (pintype "bidirectional"))
      (node (ref "S1") (pin "2") (pinfunction "2_2") (pintype "bidirectional"))
    )
    (net (code "45") (name "Net-(D2-PadA)") (class "Default")
      (node (ref "D2") (pin "A") (pinfunction "A_A") (pintype "bidirectional"))
      (node (ref "S2") (pin "2") (pinfunction "2_2") (pintype "bidirectional"))
    )
    (net (code "46") (name "Net-(D3-PadA)") (class "Default")
      (node (ref "D3") (pin "A") (pinfunction "A_A") (pintype "bidirectional"))
      (node (ref "S3") (pin "2") (pinfunction "2_2") (pintype "bidirectional"))
    )
    (net (code "47") (name "Net-(D5-PadA)") (class "Default")
      (node (ref "D5") (pin "A") (pinfunction "A_A") (pintype "bidirectional"))
      (node (ref "S5") (pin "2") (pinfunction "2_2") (pintype "bidirectional"))
    )
    (net (code "48") (name "Net-(D6-PadA)") (class "Default")
      (node (ref "D6") (pin "A") (pinfunction "A_A") (pintype "bidirectional"))
      (node (ref "S6") (pin "2") (pinfunction "2_2") (pintype "bidirectional"))
    )
    (net (code "49") (name "Net-(D7-PadA)") (class "Default")
      (node (ref "D7") (pin "A") (pinfunction "A_A") (pintype "bidirectional"))
      (node (ref "S7") (pin "2") (pinfunction "2_2") (pintype "bidirectional"))
    )
    (net (code "50") (name "Net-(D8-PadA)") (class "Default")
      (node (ref "D8") (pin "A") (pinfunction "A_A") (pintype "bidirectional"))
      (node (ref "S8") (pin "2") (pinfunction "2_2") (pintype "bidirectional"))
    )
    (net (code "51") (name "Net-(D9-PadA)") (class "Default")
      (node (ref "D9") (pin "A") (pinfunction "A_A") (pintype "bidirectional"))
      (node (ref "S9") (pin "2") (pinfunction "2_2") (pintype "bidirectional"))
    )
    (net (code "52") (name "Net-(D10-PadA)") (class "Default")
      (node (ref "D10") (pin "A") (pinfunction "A_A") (pintype "bidirectional"))
      (node (ref "S10") (pin "2") (pinfunction "2_2") (pintype "bidirectional"))
    )
    (net (code "53") (name "Net-(D11-PadA)") (class "Default")
      (node (ref "D11") (pin "A") (pinfunction "A_A") (pintype "bidirectional"))
      (node (ref "S11") (pin "2") (pinfunction "2_2") (pintype "bidirectional"))
    )
    (net (code "54") (name "Net-(D12-PadA)") (class "Default")
      (node (ref "D12") (pin "A") (pinfunction "A_A") (pintype "bidirectional"))
      (node (ref "S12") (pin "2") (pinfunction "2_2") (pintype "bidirectional"))
    )
    (net (code "55") (name "Net-(D13-PadA)") (class "Default")
      (node (ref "D13") (pin "A") (pinfunction "A_A") (pintype "bidirectional"))
      (node (ref "S13") (pin "2") (pinfunction "2_2") (pintype "bidirectional"))
    )
    (net (code "56") (name "Net-(D14-PadA)") (class "Default")
      (node (ref "D14") (pin "A") (pinfunction "A_A") (pintype "bidirectional"))
      (node (ref "S14") (pin "2") (pinfunction "2_2") (pintype "bidirectional"))
    )
    (net (code "57") (name "Net-(D15-PadA)") (class "Default")
      (node (ref "D15") (pin "A") (pinfunction "A_A") (pintype "bidirectional"))
      (node (ref "S15") (pin "2") (pinfunction "2_2") (pintype "bidirectional"))
    )
    (net (code "58") (name "Net-(D16-PadA)") (class "Default")
      (node (ref "D16") (pin "A") (pinfunction "A_A") (pintype "bidirectional"))
      (node (ref "S16") (pin "2") (pinfunction "2_2") (pintype "bidirectional"))
    )
    (net (code "59") (name "Net-(D17-PadA)") (class "Default")
      (node (ref "D17") (pin "A") (pinfunction "A_A") (pintype "bidirectional"))
      (node (ref "S17") (pin "2") (pinfunction "2_2") (pintype "bidirectional"))
    )
    (net (code "60") (name "Net-(D18-PadA)") (class "Default")
      (node (ref "D18") (pin "A") (pinfunction "A_A") (pintype "bidirectional"))
      (node (ref "S18") (pin "2") (pinfunction "2_2") (pintype "bidirectional"))
    )
    (net (code "61") (name "Net-(D19-PadA)") (class "Default")
      (node (ref "D19") (pin "A") (pinfunction "A_A") (pintype "bidirectional"))
      (node (ref "S19") (pin "2") (pinfunction "2_2") (pintype "bidirectional"))
    )
    (net (code "62") (name "Net-(D20-PadA)") (class "Default")
      (node (ref "D20") (pin "A") (pinfunction "A_A") (pintype "bidirectional"))
      (node (ref "S20") (pin "2") (pinfunction "2_2") (pintype "bidirectional"))
    )
    (net (code "63") (name "Net-(D21-C)") (class "Default")
      (node (ref "D21") (pin "K") (pinfunction "C_K") (pintype "passive"))
      (node (ref "U1") (pin "IN+") (pinfunction "IN+_IN+") (pintype "bidirectional"))
    )
    (net (code "64") (name "Net-(D21-PadA)") (class "Default")
      (node (ref "D21") (pin "A") (pinfunction "A_A") (pintype "passive"))
      (node (ref "R2") (pin "2") (pinfunction "2_2") (pintype "passive"))
      (node (ref "X1") (pin "VBUS") (pinfunction "VBUS_VBUS") (pintype "bidirectional"))
    )
    (net (code "65") (name "Net-(IC1-CONTROL)") (class "Default")
      (node (ref "IC1") (pin "3") (pinfunction "CONTROL_3") (pintype "bidirectional"))
      (node (ref "R11") (pin "2") (pinfunction "2_2") (pintype "passive"))
    )
    (net (code "66") (name "Net-(LED0-PadA)") (class "Default")
      (node (ref "LED0") (pin "A") (pinfunction "A_A") (pintype "passive"))
      (node (ref "R9") (pin "2") (pinfunction "2_2") (pintype "passive"))
    )
    (net (code "67") (name "Net-(Q1-G)") (class "Default")
      (node (ref "Q1") (pin "3") (pinfunction "G_3") (pintype "passive"))
      (node (ref "R1") (pin "2") (pinfunction "2_2") (pintype "passive"))
      (node (ref "R2") (pin "1") (pinfunction "1_1") (pintype "passive"))
    )
    (net (code "68") (name "Net-(TP2-PadTP)") (class "Default")
      (node (ref "TP2") (pin "TP") (pinfunction "TP_TP") (pintype "input"))
      (node (ref "X1") (pin "ADC_VREF") (pinfunction "ADC_VREF_ADC_VREF") (pintype "bidirectional"))
    )
    (net (code "69") (name "Net-(U2-RST)") (class "Default")
      (node (ref "R10") (pin "2") (pinfunction "2_2") (pintype "passive"))
      (node (ref "U2") (pin "16") (pinfunction "RST_16") (pintype "passive"))
    )
    (net (code "70") (name "ROW1") (class "Default")
      (node (ref "D1") (pin "K") (pinfunction "K_K") (pintype "bidirectional"))
      (node (ref "D2") (pin "K") (pinfunction "K_K") (pintype "bidirectional"))
      (node (ref "D3") (pin "K") (pinfunction "K_K") (pintype "bidirectional"))
      (node (ref "X1") (pin "GP15") (pinfunction "GP15_GP15") (pintype "bidirectional"))
    )
    (net (code "71") (name "ROW2") (class "Default")
      (node (ref "D5") (pin "K") (pinfunction "K_K") (pintype "bidirectional"))
      (node (ref "D6") (pin "K") (pinfunction "K_K") (pintype "bidirectional"))
      (node (ref "D7") (pin "K") (pinfunction "K_K") (pintype "bidirectional"))
      (node (ref "D8") (pin "K") (pinfunction "K_K") (pintype "bidirectional"))
      (node (ref "X1") (pin "GP14") (pinfunction "GP14_GP14") (pintype "bidirectional"))
    )
    (net (code "72") (name "ROW3") (class "Default")
      (node (ref "D10") (pin "K") (pinfunction "K_K") (pintype "bidirectional"))
      (node (ref "D11") (pin "K") (pinfunction "K_K") (pintype "bidirectional"))
      (node (ref "D12") (pin "K") (pinfunction "K_K") (pintype "bidirectional"))
      (node (ref "D9") (pin "K") (pinfunction "K_K") (pintype "bidirectional"))
      (node (ref "X1") (pin "GP13") (pinfunction "GP13_GP13") (pintype "bidirectional"))
    )
    (net (code "73") (name "ROW4") (class "Default")
      (node (ref "D13") (pin "K") (pinfunction "K_K") (pintype "bidirectional"))
      (node (ref "D14") (pin "K") (pinfunction "K_K") (pintype "bidirectional"))
      (node (ref "D15") (pin "K") (pinfunction "K_K") (pintype "bidirectional"))
      (node (ref "D16") (pin "K") (pinfunction "K_K") (pintype "bidirectional"))
      (node (ref "X1") (pin "GP12") (pinfunction "GP12_GP12") (pintype "bidirectional"))
    )
    (net (code "74") (name "ROW5") (class "Default")
      (node (ref "D17") (pin "K") (pinfunction "K_K") (pintype "bidirectional"))
      (node (ref "D18") (pin "K") (pinfunction "K_K") (pintype "bidirectional"))
      (node (ref "D19") (pin "K") (pinfunction "K_K") (pintype "bidirectional"))
      (node (ref "D20") (pin "K") (pinfunction "K_K") (pintype "bidirectional"))
      (node (ref "X1") (pin "GP11") (pinfunction "GP11_GP11") (pintype "bidirectional"))
    )
    (net (code "75") (name "unconnected-(IC1-NC-Pad4)") (class "Default")
      (node (ref "IC1") (pin "4") (pinfunction "NC_4") (pintype "no_connect"))
    )
    (net (code "76") (name "unconnected-(R11-Pad1)") (class "Default")
      (node (ref "R11") (pin "1") (pinfunction "1_1") (pintype "passive"))
    )
    (net (code "77") (name "unconnected-(S1-MH-PadMH2)") (class "Default")
      (node (ref "S1") (pin "MH2") (pinfunction "MH_MH2") (pintype "bidirectional"))
    )
    (net (code "78") (name "unconnected-(S1-MH-PadMH3)") (class "Default")
      (node (ref "S1") (pin "MH3") (pinfunction "MH_MH3") (pintype "bidirectional"))
    )
    (net (code "79") (name "unconnected-(S2-MH-PadMH2)") (class "Default")
      (node (ref "S2") (pin "MH2") (pinfunction "MH_MH2") (pintype "bidirectional"))
    )
    (net (code "80") (name "unconnected-(S2-MH-PadMH3)") (class "Default")
      (node (ref "S2") (pin "MH3") (pinfunction "MH_MH3") (pintype "bidirectional"))
    )
    (net (code "81") (name "unconnected-(S3-MH-PadMH2)") (class "Default")
      (node (ref "S3") (pin "MH2") (pinfunction "MH_MH2") (pintype "bidirectional"))
    )
    (net (code "82") (name "unconnected-(S3-MH-PadMH3)") (class "Default")
      (node (ref "S3") (pin "MH3") (pinfunction "MH_MH3") (pintype "bidirectional"))
    )
    (net (code "83") (name "unconnected-(S5-MH-PadMH2)") (class "Default")
      (node (ref "S5") (pin "MH2") (pinfunction "MH_MH2") (pintype "bidirectional"))
    )
    (net (code "84") (name "unconnected-(S5-MH-PadMH3)") (class "Default")
      (node (ref "S5") (pin "MH3") (pinfunction "MH_MH3") (pintype "bidirectional"))
    )
    (net (code "85") (name "unconnected-(S6-MH-PadMH2)") (class "Default")
      (node (ref "S6") (pin "MH2") (pinfunction "MH_MH2") (pintype "bidirectional"))
    )
    (net (code "86") (name "unconnected-(S6-MH-PadMH3)") (class "Default")
      (node (ref "S6") (pin "MH3") (pinfunction "MH_MH3") (pintype "bidirectional"))
    )
    (net (code "87") (name "unconnected-(S7-MH-PadMH2)") (class "Default")
      (node (ref "S7") (pin "MH2") (pinfunction "MH_MH2") (pintype "bidirectional"))
    )
    (net (code "88") (name "unconnected-(S7-MH-PadMH3)") (class "Default")
      (node (ref "S7") (pin "MH3") (pinfunction "MH_MH3") (pintype "bidirectional"))
    )
    (net (code "89") (name "unconnected-(S9-MH-PadMH2)") (class "Default")
      (node (ref "S9") (pin "MH2") (pinfunction "MH_MH2") (pintype "bidirectional"))
    )
    (net (code "90") (name "unconnected-(S9-MH-PadMH3)") (class "Default")
      (node (ref "S9") (pin "MH3") (pinfunction "MH_MH3") (pintype "bidirectional"))
    )
    (net (code "91") (name "unconnected-(S10-MH-PadMH2)") (class "Default")
      (node (ref "S10") (pin "MH2") (pinfunction "MH_MH2") (pintype "bidirectional"))
    )
    (net (code "92") (name "unconnected-(S10-MH-PadMH3)") (class "Default")
      (node (ref "S10") (pin "MH3") (pinfunction "MH_MH3") (pintype "bidirectional"))
    )
    (net (code "93") (name "unconnected-(S11-MH-PadMH2)") (class "Default")
      (node (ref "S11") (pin "MH2") (pinfunction "MH_MH2") (pintype "bidirectional"))
    )
    (net (code "94") (name "unconnected-(S11-MH-PadMH3)") (class "Default")
      (node (ref "S11") (pin "MH3") (pinfunction "MH_MH3") (pintype "bidirectional"))
    )
    (net (code "95") (name "unconnected-(S12-MH-PadMH2)") (class "Default")
      (node (ref "S12") (pin "MH2") (pinfunction "MH_MH2") (pintype "bidirectional"))
    )
    (net (code "96") (name "unconnected-(S12-MH-PadMH3)") (class "Default")
      (node (ref "S12") (pin "MH3") (pinfunction "MH_MH3") (pintype "bidirectional"))
    )
    (net (code "97") (name "unconnected-(S13-MH-PadMH2)") (class "Default")
      (node (ref "S13") (pin "MH2") (pinfunction "MH_MH2") (pintype "bidirectional"))
    )
    (net (code "98") (name "unconnected-(S13-MH-PadMH3)") (class "Default")
      (node (ref "S13") (pin "MH3") (pinfunction "MH_MH3") (pintype "bidirectional"))
    )
    (net (code "99") (name "unconnected-(S14-MH-PadMH2)") (class "Default")
      (node (ref "S14") (pin "MH2") (pinfunction "MH_MH2") (pintype "bidirectional"))
    )
    (net (code "100") (name "unconnected-(S14-MH-PadMH3)") (class "Default")
      (node (ref "S14") (pin "MH3") (pinfunction "MH_MH3") (pintype "bidirectional"))
    )
    (net (code "101") (name "unconnected-(S15-MH-PadMH2)") (class "Default")
      (node (ref "S15") (pin "MH2") (pinfunction "MH_MH2") (pintype "bidirectional"))
    )
    (net (code "102") (name "unconnected-(S15-MH-PadMH3)") (class "Default")
      (node (ref "S15") (pin "MH3") (pinfunction "MH_MH3") (pintype "bidirectional"))
    )
    (net (code "103") (name "unconnected-(S16-MH-PadMH2)") (class "Default")
      (node (ref "S16") (pin "MH2") (pinfunction "MH_MH2") (pintype "bidirectional"))
    )
    (net (code "104") (name "unconnected-(S16-MH-PadMH3)") (class "Default")
      (node (ref "S16") (pin "MH3") (pinfunction "MH_MH3") (pintype "bidirectional"))
    )
    (net (code "105") (name "unconnected-(S17-MH-PadMH2)") (class "Default")
      (node (ref "S17") (pin "MH2") (pinfunction "MH_MH2") (pintype "bidirectional"))
    )
    (net (code "106") (name "unconnected-(S17-MH-PadMH3)") (class "Default")
      (node (ref "S17") (pin "MH3") (pinfunction "MH_MH3") (pintype "bidirectional"))
    )
    (net (code "107") (name "unconnected-(S18-MH-PadMH2)") (class "Default")
      (node (ref "S18") (pin "MH2") (pinfunction "MH_MH2") (pintype "bidirectional"))
    )
    (net (code "108") (name "unconnected-(S18-MH-PadMH3)") (class "Default")
      (node (ref "S18") (pin "MH3") (pinfunction "MH_MH3") (pintype "bidirectional"))
    )
    (net (code "109") (name "unconnected-(S19-MH-PadMH2)") (class "Default")
      (node (ref "S19") (pin "MH2") (pinfunction "MH_MH2") (pintype "bidirectional"))
    )
    (net (code "110") (name "unconnected-(S19-MH-PadMH3)") (class "Default")
      (node (ref "S19") (pin "MH3") (pinfunction "MH_MH3") (pintype "bidirectional"))
    )
    (net (code "111") (name "unconnected-(S20-MH-PadMH2)") (class "Default")
      (node (ref "S20") (pin "MH2") (pinfunction "MH_MH2") (pintype "bidirectional"))
    )
    (net (code "112") (name "unconnected-(S20-MH-PadMH3)") (class "Default")
      (node (ref "S20") (pin "MH3") (pinfunction "MH_MH3") (pintype "bidirectional"))
    )
    (net (code "113") (name "unconnected-(U1-PadBAT+)") (class "Default")
      (node (ref "U1") (pin "BAT+") (pinfunction "BAT+_BAT+") (pintype "bidirectional"))
    )
    (net (code "114") (name "unconnected-(U1-PadBAT-)") (class "Default")
      (node (ref "U1") (pin "BAT-") (pinfunction "BAT-_BAT-") (pintype "bidirectional"))
    )
    (net (code "115") (name "unconnected-(U2-9-Pad23)") (class "Default")
      (node (ref "U2") (pin "23") (pinfunction "9_23") (pintype "passive"))
    )
    (net (code "116") (name "unconnected-(U2-10-Pad22)") (class "Default")
      (node (ref "U2") (pin "22") (pinfunction "10_22") (pintype "passive"))
    )
    (net (code "117") (name "unconnected-(U2-11-Pad21)") (class "Default")
      (node (ref "U2") (pin "21") (pinfunction "11_21") (pintype "passive"))
    )
    (net (code "118") (name "unconnected-(U2-12-Pad20)") (class "Default")
      (node (ref "U2") (pin "20") (pinfunction "12_20") (pintype "passive"))
    )
    (net (code "119") (name "unconnected-(U2-13-Pad19)") (class "Default")
      (node (ref "U2") (pin "19") (pinfunction "13_19") (pintype "passive"))
    )
    (net (code "120") (name "unconnected-(U2-AREF-Pad14)") (class "Default")
      (node (ref "U2") (pin "14") (pinfunction "AREF_14") (pintype "passive"))
    )
    (net (code "121") (name "unconnected-(U2-EN-Pad18)") (class "Default")
      (node (ref "U2") (pin "18") (pinfunction "EN_18") (pintype "passive"))
    )
    (net (code "122") (name "unconnected-(U2-VBAT-Pad17)") (class "Default")
      (node (ref "U2") (pin "17") (pinfunction "VBAT_17") (pintype "passive"))
    )
    (net (code "123") (name "unconnected-(U3-Pad1)") (class "Default")
      (node (ref "U3") (pin "1") (pinfunction "1_1") (pintype "bidirectional"))
    )
    (net (code "124") (name "unconnected-(U3-Pad2)") (class "Default")
      (node (ref "U3") (pin "2") (pinfunction "2_2") (pintype "bidirectional"))
    )
    (net (code "125") (name "unconnected-(X1-GND-PadGND@1)") (class "Default")
      (node (ref "X1") (pin "GND@1") (pinfunction "GND_GND@1") (pintype "bidirectional"))
    )
    (net (code "126") (name "unconnected-(X1-GND-PadGND@2)") (class "Default")
      (node (ref "X1") (pin "GND@2") (pinfunction "GND_GND@2") (pintype "bidirectional"))
    )
    (net (code "127") (name "unconnected-(X1-GND-PadGND@3)") (class "Default")
      (node (ref "X1") (pin "GND@3") (pinfunction "GND_GND@3") (pintype "bidirectional"))
    )
    (net (code "128") (name "unconnected-(X1-GND-PadGND@4)") (class "Default")
      (node (ref "X1") (pin "GND@4") (pinfunction "GND_GND@4") (pintype "bidirectional"))
    )
    (net (code "129") (name "unconnected-(X1-GND-PadGND@6)") (class "Default")
      (node (ref "X1") (pin "GND@6") (pinfunction "GND_GND@6") (pintype "bidirectional"))
    )
    (net (code "130") (name "unconnected-(X1-GND-PadGND@7)") (class "Default")
      (node (ref "X1") (pin "GND@7") (pinfunction "GND_GND@7") (pintype "bidirectional"))
    )
    (net (code "131") (name "unconnected-(X1-Pad3V3_EN)") (class "Default")
      (node (ref "X1") (pin "3V3_EN") (pinfunction "3V3_EN_3V3_EN") (pintype "bidirectional"))
    )
    (net (code "132") (name "unconnected-(X1-PadAGND)") (class "Default")
      (node (ref "X1") (pin "AGND") (pinfunction "AGND_AGND") (pintype "bidirectional"))
    )
    (net (code "133") (name "unconnected-(X1-PadGP2)") (class "Default")
      (node (ref "X1") (pin "GP2") (pinfunction "GP2_GP2") (pintype "bidirectional"))
    )
    (net (code "134") (name "unconnected-(X1-PadGP3)") (class "Default")
      (node (ref "X1") (pin "GP3") (pinfunction "GP3_GP3") (pintype "bidirectional"))
    )
    (net (code "135") (name "unconnected-(X1-PadGP10)") (class "Default")
      (node (ref "X1") (pin "GP10") (pinfunction "GP10_GP10") (pintype "bidirectional"))
    )
    (net (code "136") (name "unconnected-(X1-PadGP17)") (class "Default")
      (node (ref "X1") (pin "GP17") (pinfunction "GP17_GP17") (pintype "bidirectional"))
    )
  )
)
